# Flight_Controller2.net
KiCad netlist of a schematic drawn in Altium Designer
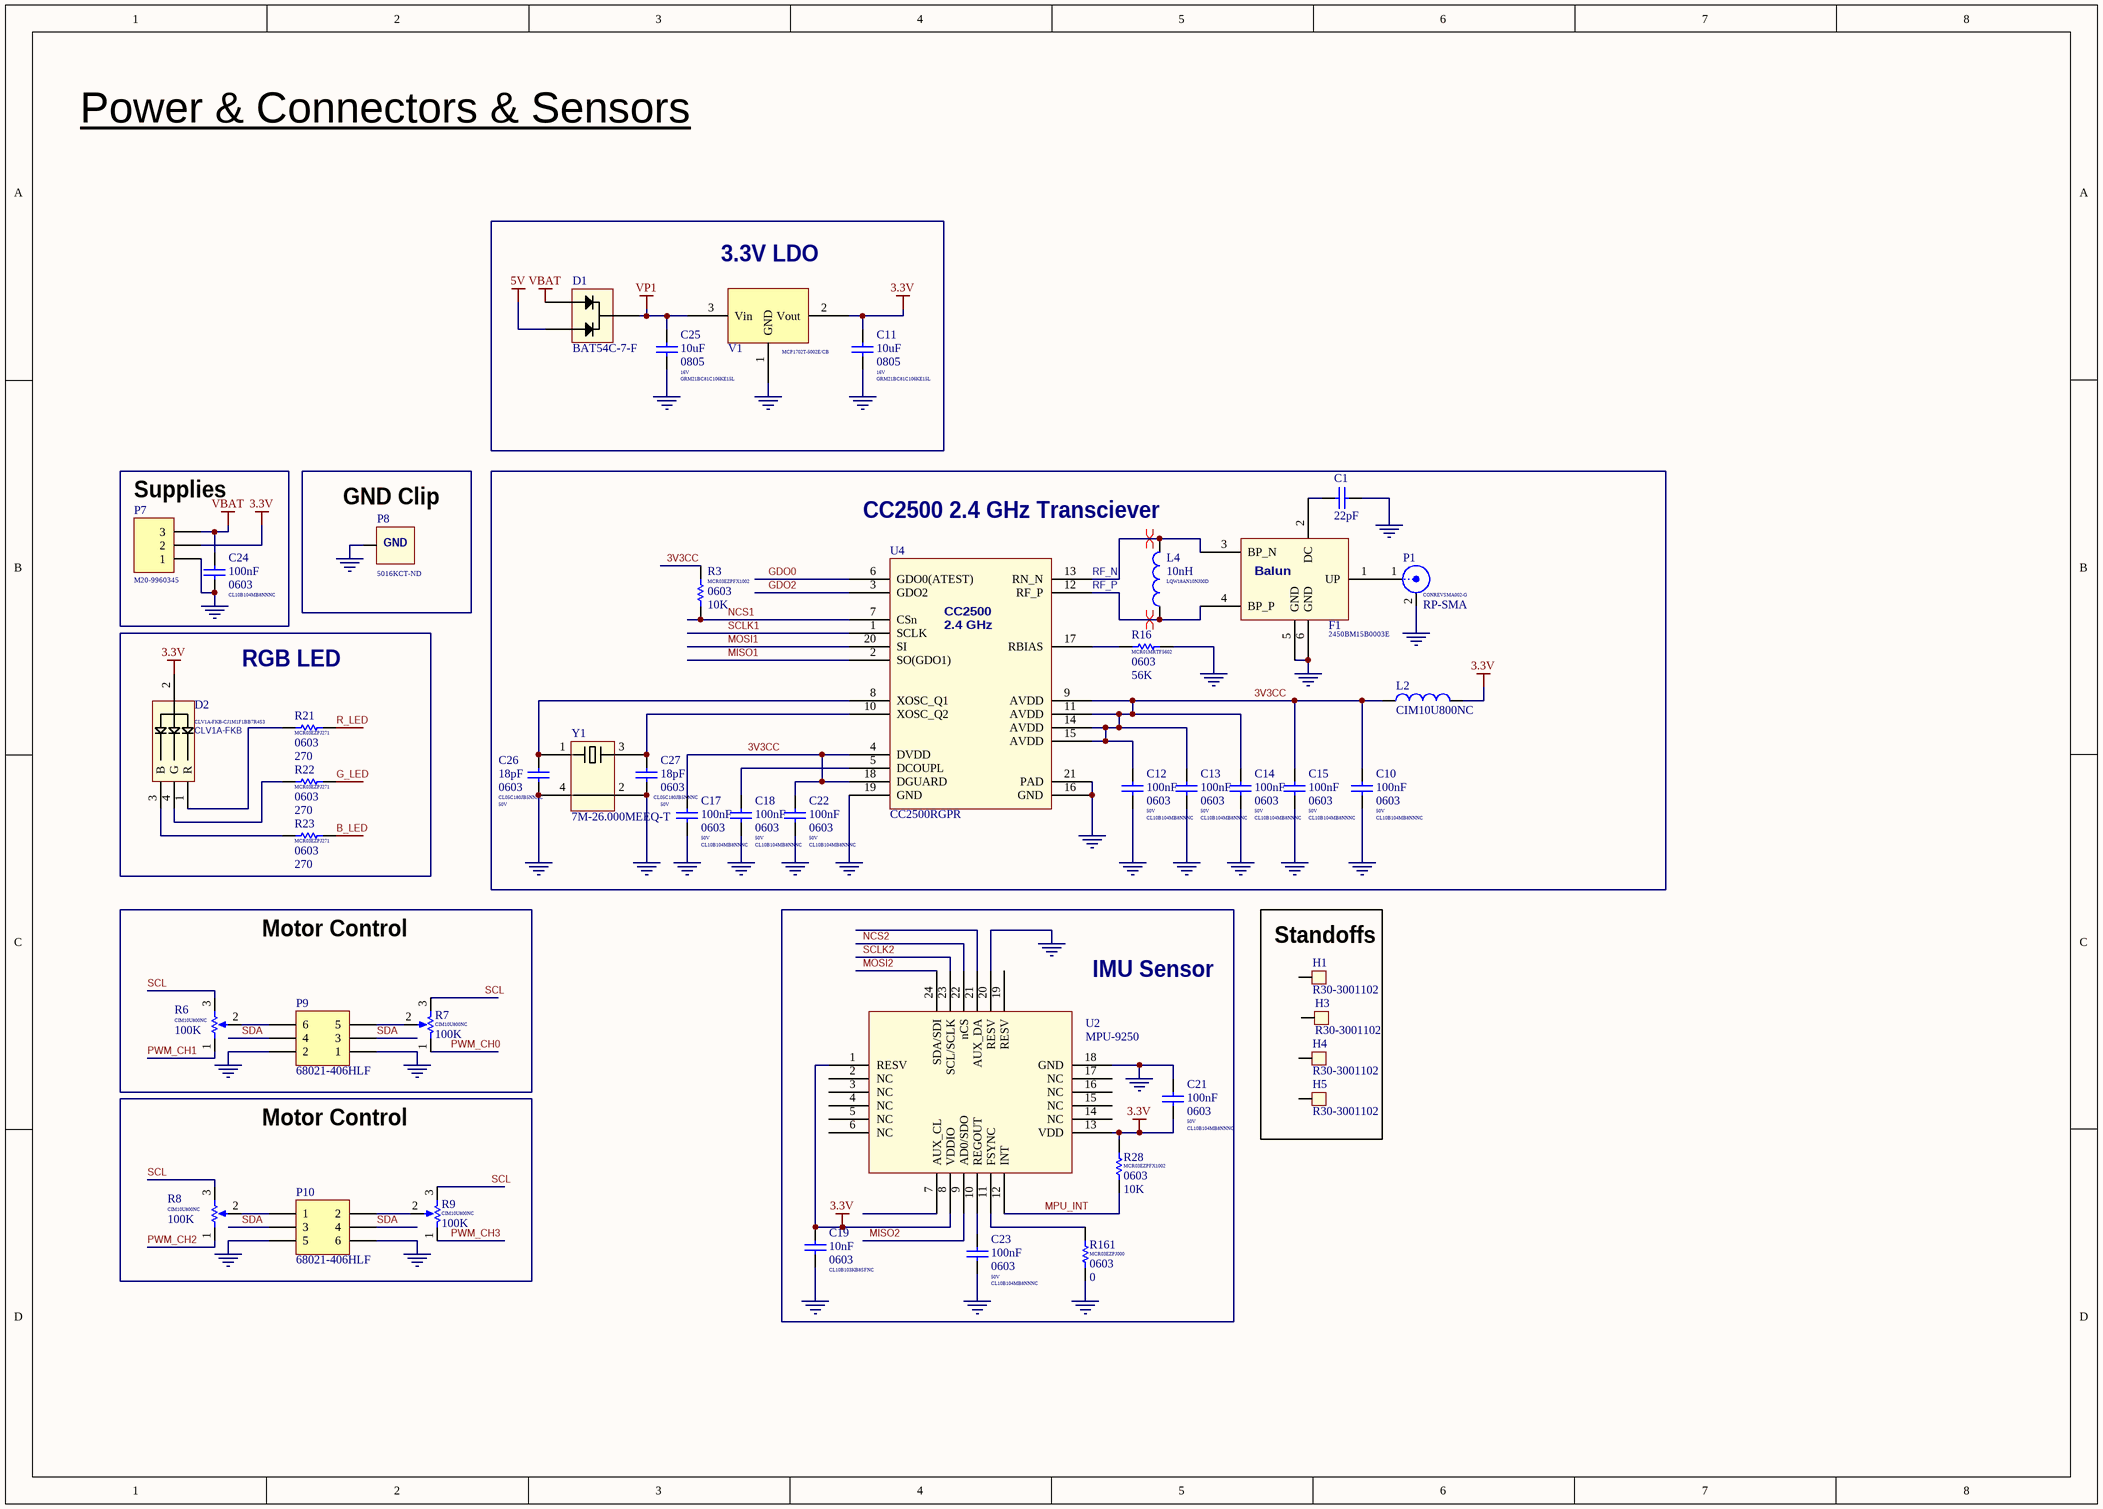
[diagram p0: Flight_Controller2.SchDoc]

(export (version "E")
  (design (tool "Eeschema 10.0.6"))
  (components
    (comp (ref "C1")
      (value "22pF")
      (footprint "1608[0603]C")
      (description "Capacitor (Semiconductor SIM Model)")
      (fields (field (name "Comment") "GRM1885C1H220FA01D") (field (name "PUBLISHER") "Altium Limited"))
      (libsource (lib "Miscellaneous Devices") (part "Cap Semi"))
    )
    (comp (ref "C10")
      (value "CL10B104MB8NNNC")
      (footprint "1608[0603]C")
      (description "Capacitor (Semiconductor SIM Model)")
      (fields
        (field (name "PACKAGEREFERENCE") "0603")
        (field (name "ALTIUM_VALUE") "100nF")
        (field (name "VOLTAGE") "50V")
      )
      (libsource (lib "Miscellaneous Devices") (part "Cap Semi"))
    )
    (comp (ref "C11")
      (value "GRM21BC81C106KE15L")
      (footprint "6-0805_MC")
      (description "Capacitor (Semiconductor SIM Model)")
      (fields
        (field (name "PACKAGEREFERENCE") "0805")
        (field (name "ALTIUM_VALUE") "10uF")
        (field (name "PART_NUMBER") "CL10B104MB8NNNC")
        (field (name "VOLTAGE") "16V")
      )
      (libsource (lib "Miscellaneous Devices") (part "Cap Semi"))
    )
    (comp (ref "C12")
      (value "CL10B104MB8NNNC")
      (footprint "1608[0603]C")
      (description "Capacitor (Semiconductor SIM Model)")
      (fields
        (field (name "PACKAGEREFERENCE") "0603")
        (field (name "ALTIUM_VALUE") "100nF")
        (field (name "VOLTAGE") "50V")
      )
      (libsource (lib "Miscellaneous Devices") (part "Cap Semi"))
    )
    (comp (ref "C13")
      (value "CL10B104MB8NNNC")
      (footprint "1608[0603]C")
      (description "Capacitor (Semiconductor SIM Model)")
      (fields
        (field (name "PACKAGEREFERENCE") "0603")
        (field (name "ALTIUM_VALUE") "100nF")
        (field (name "VOLTAGE") "50V")
      )
      (libsource (lib "Miscellaneous Devices") (part "Cap Semi"))
    )
    (comp (ref "C14")
      (value "CL10B104MB8NNNC")
      (footprint "1608[0603]C")
      (description "Capacitor (Semiconductor SIM Model)")
      (fields
        (field (name "PACKAGEREFERENCE") "0603")
        (field (name "ALTIUM_VALUE") "100nF")
        (field (name "VOLTAGE") "50V")
      )
      (libsource (lib "Miscellaneous Devices") (part "Cap Semi"))
    )
    (comp (ref "C15")
      (value "CL10B104MB8NNNC")
      (footprint "1608[0603]C")
      (description "Capacitor (Semiconductor SIM Model)")
      (fields
        (field (name "PACKAGEREFERENCE") "0603")
        (field (name "ALTIUM_VALUE") "100nF")
        (field (name "VOLTAGE") "50V")
      )
      (libsource (lib "Miscellaneous Devices") (part "Cap Semi"))
    )
    (comp (ref "C17")
      (value "CL10B104MB8NNNC")
      (footprint "1608[0603]C")
      (description "Capacitor (Semiconductor SIM Model)")
      (fields
        (field (name "PACKAGEREFERENCE") "0603")
        (field (name "ALTIUM_VALUE") "100nF")
        (field (name "VOLTAGE") "50V")
      )
      (libsource (lib "Miscellaneous Devices") (part "Cap Semi"))
    )
    (comp (ref "C18")
      (value "CL10B104MB8NNNC")
      (footprint "1608[0603]C")
      (description "Capacitor (Semiconductor SIM Model)")
      (fields
        (field (name "PACKAGEREFERENCE") "0603")
        (field (name "ALTIUM_VALUE") "100nF")
        (field (name "VOLTAGE") "50V")
      )
      (libsource (lib "Miscellaneous Devices") (part "Cap Semi"))
    )
    (comp (ref "C19")
      (value "CL10B103KB8SFNC")
      (footprint "1608[0603]C")
      (description "Capacitor (Semiconductor SIM Model)")
      (fields
        (field (name "PACKAGEREFERENCE") "0603")
        (field (name "ALTIUM_VALUE") "10nF")
        (field (name "PUBLISHER") "Altium Limited")
      )
      (libsource (lib "Miscellaneous Devices") (part "Cap Semi"))
    )
    (comp (ref "C21")
      (value "CL10B104MB8NNNC")
      (footprint "1608[0603]C")
      (description "Capacitor (Semiconductor SIM Model)")
      (fields
        (field (name "PACKAGEREFERENCE") "0603")
        (field (name "ALTIUM_VALUE") "100nF")
        (field (name "VOLTAGE") "50V")
      )
      (libsource (lib "Miscellaneous Devices") (part "Cap Semi"))
    )
    (comp (ref "C22")
      (value "CL10B104MB8NNNC")
      (footprint "1608[0603]C")
      (description "Capacitor (Semiconductor SIM Model)")
      (fields
        (field (name "PACKAGEREFERENCE") "0603")
        (field (name "ALTIUM_VALUE") "100nF")
        (field (name "VOLTAGE") "50V")
      )
      (libsource (lib "Miscellaneous Devices") (part "Cap Semi"))
    )
    (comp (ref "C23")
      (value "CL10B104MB8NNNC")
      (footprint "1608[0603]C")
      (description "Capacitor (Semiconductor SIM Model)")
      (fields
        (field (name "PACKAGEREFERENCE") "0603")
        (field (name "ALTIUM_VALUE") "100nF")
        (field (name "VOLTAGE") "50V")
      )
      (libsource (lib "Miscellaneous Devices") (part "Cap Semi"))
    )
    (comp (ref "C24")
      (value "CL10B104MB8NNNC")
      (footprint "1608[0603]C")
      (description "Capacitor (Semiconductor SIM Model)")
      (fields (field (name "PACKAGEREFERENCE") "0603") (field (name "ALTIUM_VALUE") "100nF"))
      (libsource (lib "Miscellaneous Devices") (part "Cap Semi"))
    )
    (comp (ref "C25")
      (value "GRM21BC81C106KE15L")
      (footprint "6-0805_MC")
      (description "Capacitor (Semiconductor SIM Model)")
      (fields
        (field (name "PACKAGEREFERENCE") "0805")
        (field (name "ALTIUM_VALUE") "10uF")
        (field (name "PART_NUMBER") "CL10B104MB8NNNC")
        (field (name "VOLTAGE") "16V")
      )
      (libsource (lib "Miscellaneous Devices") (part "Cap Semi"))
    )
    (comp (ref "C26")
      (value "CL05C180JB5NNNC")
      (footprint "1608[0603]C")
      (description "Capacitor (Semiconductor SIM Model)")
      (fields
        (field (name "PACKAGEREFERENCE") "0603")
        (field (name "ALTIUM_VALUE") "18pF")
        (field (name "VOLTAGE") "50V")
      )
      (libsource (lib "Miscellaneous Devices") (part "Cap Semi"))
    )
    (comp (ref "C27")
      (value "CL05C180JB5NNNC")
      (footprint "1608[0603]C")
      (description "Capacitor (Semiconductor SIM Model)")
      (fields
        (field (name "PACKAGEREFERENCE") "0603")
        (field (name "ALTIUM_VALUE") "18pF")
        (field (name "VOLTAGE") "50V")
      )
      (libsource (lib "Miscellaneous Devices") (part "Cap Semi"))
    )
    (comp (ref "D1")
      (value "BAT54C-7-F")
      (footprint "SOT-23B_M_3D")
      (description "Bat45C")
      (libsource (lib "bat45") (part "Bat45C"))
    )
    (comp (ref "D2")
      (value "CLV1A-FKB-CJ1M1F1BB7R4S3")
      (footprint "CLV1A-FKB_RGB_3D")
      (description "SMT RGB LED")
      (fields (field (name "ALTIUM_UNNAMED_1") "CLV1A-FKB"))
      (libsource (lib "RGB_LED") (part "RGB_LED_SMT"))
    )
    (comp (ref "F1")
      (value "2450BM15B0003E")
      (footprint "Balun")
      (description "2450BM15B0003")
      (libsource (lib "2450BM15B0003") (part "BALUN_2_4_GHZ"))
    )
    (comp (ref "H1")
      (value "R30-3001102")
      (footprint "M3_Standoff_3")
      (description "stand_off")
      (libsource (lib "pcb_standoff") (part "stand_off"))
    )
    (comp (ref "H3")
      (value "R30-3001102")
      (footprint "M3_Standoff_3")
      (description "stand_off")
      (libsource (lib "pcb_standoff") (part "stand_off"))
    )
    (comp (ref "H4")
      (value "R30-3001102")
      (footprint "M3_Standoff_3")
      (description "stand_off")
      (libsource (lib "pcb_standoff") (part "stand_off"))
    )
    (comp (ref "H5")
      (value "R30-3001102")
      (footprint "M3_Standoff_3")
      (description "stand_off")
      (libsource (lib "pcb_standoff") (part "stand_off"))
    )
    (comp (ref "L2")
      (value "CIM10U800NC")
      (footprint "1608[0603]L")
      (description "Inductor")
      (libsource (lib "Miscellaneous Devices") (part "Inductor"))
    )
    (comp (ref "L4")
      (value "LQW18AN10NJ00D")
      (footprint "1608[0603]L")
      (description "Inductor")
      (fields (field (name "ALTIUM_VALUE") "10nH"))
      (libsource (lib "Miscellaneous Devices") (part "Inductor"))
    )
    (comp (ref "P1")
      (value "CONREVSMA002-G")
      (footprint "SMA1")
      (description "SMB Straight Connector")
      (fields (field (name "PART #") "5-1814832-1") (field (name "SMA") "RP-SMA"))
      (libsource (lib "Miscellaneous Connectors") (part "SMB"))
    )
    (comp (ref "P7")
      (value "M20-9960345")
      (footprint "HDR1X3")
      (description "Header, 3-Pin")
      (fields (field (name "PUBLISHER") "Altium Limited"))
      (libsource (lib "Miscellaneous Connectors") (part "Header 3"))
    )
    (comp (ref "P8")
      (value "5016KCT-ND")
      (footprint "GND_CLIP3")
      (description "GND_CLIP")
      (libsource (lib "GND_CLIP") (part "GND_CLIP"))
    )
    (comp (ref "P9")
      (value "68021-406HLF")
      (footprint "HDR2X3_3D2")
      (description "Header, 3-Pin, Dual row")
      (fields (field (name "PUBLISHER") "Altium Limited"))
      (libsource (lib "Miscellaneous Connectors") (part "Header 3X2"))
    )
    (comp (ref "P10")
      (value "68021-406HLF")
      (footprint "HDR2X3_3D2")
      (description "Header, 3-Pin, Dual row")
      (fields (field (name "PUBLISHER") "Altium Limited"))
      (libsource (lib "") (part "Header 3X2_1"))
    )
    (comp (ref "R3")
      (value "MCR03EZPFX1002")
      (footprint "1608[0603]R")
      (description "Resistor")
      (fields
        (field (name "PACKAGEREFERENCE") "0603")
        (field (name "ALTIUM_VALUE") "10K")
        (field (name "PART_NUMBER") "MCR03ERTJ102")
      )
      (libsource (lib "Miscellaneous Devices") (part "Res1"))
    )
    (comp (ref "R6")
      (value "CIM10U800NC")
      (footprint "1608[0603]TRI")
      (description "Potentiometer")
      (fields (field (name "ALTIUM_VALUE") "100K") (field (name "PUBLISHER") "Altium Limited"))
      (libsource (lib "Miscellaneous Devices") (part "RPot"))
    )
    (comp (ref "R7")
      (value "CIM10U800NC")
      (footprint "1608[0603]TRI")
      (description "Potentiometer")
      (fields (field (name "ALTIUM_VALUE") "100K") (field (name "PUBLISHER") "Altium Limited"))
      (libsource (lib "Miscellaneous Devices") (part "RPot"))
    )
    (comp (ref "R8")
      (value "CIM10U800NC")
      (footprint "1608[0603]TRI")
      (description "Potentiometer")
      (fields (field (name "ALTIUM_VALUE") "100K") (field (name "PUBLISHER") "Altium Limited"))
      (libsource (lib "Miscellaneous Devices") (part "RPot"))
    )
    (comp (ref "R9")
      (value "CIM10U800NC")
      (footprint "1608[0603]TRI")
      (description "Potentiometer")
      (fields (field (name "ALTIUM_VALUE") "100K") (field (name "PUBLISHER") "Altium Limited"))
      (libsource (lib "Miscellaneous Devices") (part "RPot"))
    )
    (comp (ref "R16")
      (value "MCR01MRTF5602")
      (footprint "1608[0603]R")
      (description "Resistor")
      (fields
        (field (name "PACKAGEREFERENCE") "0603")
        (field (name "ALTIUM_VALUE") "56K")
        (field (name "PART_NUMBER") "MCR03ERTJ102")
      )
      (libsource (lib "Miscellaneous Devices") (part "Res1"))
    )
    (comp (ref "R21")
      (value "MCR03EZPJ271")
      (footprint "1608[0603]R")
      (description "Resistor")
      (fields
        (field (name "PACKAGEREFERENCE") "0603")
        (field (name "ALTIUM_VALUE") "270")
        (field (name "PART_NUMBER") "MCR03ERTJ102")
      )
      (libsource (lib "Miscellaneous Devices") (part "Res1"))
    )
    (comp (ref "R22")
      (value "MCR03EZPJ271")
      (footprint "1608[0603]R")
      (description "Resistor")
      (fields
        (field (name "PACKAGEREFERENCE") "0603")
        (field (name "ALTIUM_VALUE") "270")
        (field (name "PART_NUMBER") "MCR03ERTJ102")
      )
      (libsource (lib "Miscellaneous Devices") (part "Res1"))
    )
    (comp (ref "R23")
      (value "MCR03EZPJ271")
      (footprint "1608[0603]R")
      (description "Resistor")
      (fields
        (field (name "PACKAGEREFERENCE") "0603")
        (field (name "ALTIUM_VALUE") "270")
        (field (name "PART_NUMBER") "MCR03ERTJ102")
      )
      (libsource (lib "Miscellaneous Devices") (part "Res1"))
    )
    (comp (ref "R28")
      (value "MCR03EZPFX1002")
      (footprint "1608[0603]R")
      (description "Resistor")
      (fields
        (field (name "PACKAGEREFERENCE") "0603")
        (field (name "ALTIUM_VALUE") "10K")
        (field (name "PART_NUMBER") "MCR03ERTJ102")
      )
      (libsource (lib "Miscellaneous Devices") (part "Res1"))
    )
    (comp (ref "R161")
      (value "MCR03EZPJ000")
      (footprint "1608[0603]R")
      (description "Resistor")
      (fields
        (field (name "PACKAGEREFERENCE") "0603")
        (field (name "ALTIUM_VALUE") "0")
        (field (name "PART_NUMBER") "MCR03ERTJ102")
      )
      (libsource (lib "Miscellaneous Devices") (part "Res1"))
    )
    (comp (ref "U2")
      (value "MPU-9250")
      (footprint "QFN-24/3MM")
      (libsource (lib "MPU9250") (part "MPU-9250_LIB"))
    )
    (comp (ref "U4")
      (value "CC2500RGPR")
      (footprint "QFN50P400X400-20VM")
      (description "CC2500_2_4_ghz")
      (libsource (lib "CC2500") (part "CC2500_2_4_ghz"))
    )
    (comp (ref "V1")
      (value "MCP1702T-5002E/CB")
      (footprint "SOT-23B_M_3D")
      (description "MCP1700 3.3V REG")
      (libsource (lib "MCP1700") (part "MCP1700"))
    )
    (comp (ref "Y1")
      (value "7M-26.000MEEQ-T")
      (footprint "3225_Crystal")
      (description "26 MHz Crystal 3225")
      (libsource (lib "12MHz_micro_crystal") (part "12MHz_Crystal"))
    )
  )
  (nets
    (net (code "1") (name "/3V3CC") (class "Default")
      (node (ref "C10") (pin "2") (pinfunction "2_2") (pintype "passive"))
      (node (ref "C12") (pin "2") (pinfunction "2_2") (pintype "passive"))
      (node (ref "C13") (pin "2") (pinfunction "2_2") (pintype "passive"))
      (node (ref "C14") (pin "2") (pinfunction "2_2") (pintype "passive"))
      (node (ref "C15") (pin "2") (pinfunction "2_2") (pintype "passive"))
      (node (ref "C17") (pin "2") (pinfunction "2_2") (pintype "passive"))
      (node (ref "C22") (pin "2") (pinfunction "2_2") (pintype "passive"))
      (node (ref "L2") (pin "2") (pinfunction "2_2") (pintype "passive"))
      (node (ref "R3") (pin "2") (pinfunction "2_2") (pintype "passive"))
      (node (ref "U4") (pin "11") (pinfunction "AVDD_11") (pintype "passive"))
      (node (ref "U4") (pin "14") (pinfunction "AVDD_14") (pintype "passive"))
      (node (ref "U4") (pin "15") (pinfunction "AVDD_15") (pintype "passive"))
      (node (ref "U4") (pin "18") (pinfunction "DGUARD_18") (pintype "passive"))
      (node (ref "U4") (pin "4") (pinfunction "DVDD_4") (pintype "passive"))
      (node (ref "U4") (pin "9") (pinfunction "AVDD_9") (pintype "passive"))
    )
    (net (code "2") (name "/B_LED") (class "Default")
      (node (ref "R23") (pin "2") (pinfunction "2_2") (pintype "passive"))
    )
    (net (code "3") (name "/GDO0") (class "Default")
      (node (ref "U4") (pin "6") (pinfunction "GDO0(ATEST)_6") (pintype "passive"))
    )
    (net (code "4") (name "/GDO2") (class "Default")
      (node (ref "U4") (pin "3") (pinfunction "GDO2_3") (pintype "passive"))
    )
    (net (code "5") (name "/G_LED") (class "Default")
      (node (ref "R22") (pin "2") (pinfunction "2_2") (pintype "passive"))
    )
    (net (code "6") (name "/MISO1") (class "Default")
      (node (ref "U4") (pin "2") (pinfunction "SO(GDO1)_2") (pintype "passive"))
    )
    (net (code "7") (name "/MISO2") (class "Default")
      (node (ref "U2") (pin "9") (pinfunction "AD0/SDO_9") (pintype "passive"))
    )
    (net (code "8") (name "/MOSI1") (class "Default")
      (node (ref "U4") (pin "20") (pinfunction "SI_20") (pintype "passive"))
    )
    (net (code "9") (name "/MOSI2") (class "Default")
      (node (ref "U2") (pin "24") (pinfunction "SDA/SDI_24") (pintype "passive"))
    )
    (net (code "10") (name "/MPU_INT") (class "Default")
      (node (ref "R28") (pin "1") (pinfunction "1_1") (pintype "passive"))
      (node (ref "U2") (pin "12") (pinfunction "INT_12") (pintype "passive"))
    )
    (net (code "11") (name "/NCS1") (class "Default")
      (node (ref "R3") (pin "1") (pinfunction "1_1") (pintype "passive"))
      (node (ref "U4") (pin "7") (pinfunction "CSn_7") (pintype "passive"))
    )
    (net (code "12") (name "/NCS2") (class "Default")
      (node (ref "U2") (pin "22") (pinfunction "nCS_22") (pintype "passive"))
    )
    (net (code "13") (name "/PWM_CH0") (class "Default")
      (node (ref "R7") (pin "1") (pinfunction "1_1") (pintype "passive"))
    )
    (net (code "14") (name "/PWM_CH1") (class "Default")
      (node (ref "R6") (pin "1") (pinfunction "1_1") (pintype "passive"))
    )
    (net (code "15") (name "/PWM_CH2") (class "Default")
      (node (ref "R8") (pin "1") (pinfunction "1_1") (pintype "passive"))
    )
    (net (code "16") (name "/PWM_CH3") (class "Default")
      (node (ref "R9") (pin "1") (pinfunction "1_1") (pintype "passive"))
    )
    (net (code "17") (name "/RF_N") (class "Default")
      (node (ref "F1") (pin "3") (pinfunction "BP_N_3") (pintype "passive"))
      (node (ref "L4") (pin "1") (pinfunction "1_1") (pintype "passive"))
      (node (ref "U4") (pin "13") (pinfunction "RN_N_13") (pintype "passive"))
    )
    (net (code "18") (name "/RF_P") (class "Default")
      (node (ref "F1") (pin "4") (pinfunction "BP_P_4") (pintype "passive"))
      (node (ref "L4") (pin "2") (pinfunction "2_2") (pintype "passive"))
      (node (ref "U4") (pin "12") (pinfunction "RF_P_12") (pintype "passive"))
    )
    (net (code "19") (name "/R_LED") (class "Default")
      (node (ref "R21") (pin "2") (pinfunction "2_2") (pintype "passive"))
    )
    (net (code "20") (name "/SCL") (class "Default")
      (node (ref "R6") (pin "3") (pinfunction "2_3") (pintype "passive"))
      (node (ref "R7") (pin "3") (pinfunction "2_3") (pintype "passive"))
      (node (ref "R8") (pin "3") (pinfunction "2_3") (pintype "passive"))
      (node (ref "R9") (pin "3") (pinfunction "2_3") (pintype "passive"))
    )
    (net (code "21") (name "/SCLK1") (class "Default")
      (node (ref "U4") (pin "1") (pinfunction "SCLK_1") (pintype "passive"))
    )
    (net (code "22") (name "/SCLK2") (class "Default")
      (node (ref "U2") (pin "23") (pinfunction "SCL/SCLK_23") (pintype "passive"))
    )
    (net (code "23") (name "/SDA") (class "Default")
      (node (ref "P10") (pin "3") (pinfunction "3_3") (pintype "passive"))
      (node (ref "P10") (pin "4") (pinfunction "4_4") (pintype "passive"))
      (node (ref "P9") (pin "3") (pinfunction "3_3") (pintype "passive"))
      (node (ref "P9") (pin "4") (pinfunction "4_4") (pintype "passive"))
    )
    (net (code "24") (name "3.3V") (class "Default")
      (node (ref "C11") (pin "2") (pinfunction "2_2") (pintype "passive"))
      (node (ref "C19") (pin "2") (pinfunction "2_2") (pintype "passive"))
      (node (ref "C21") (pin "1") (pinfunction "1_1") (pintype "passive"))
      (node (ref "D2") (pin "2") (pinfunction "V+_2") (pintype "passive"))
      (node (ref "L2") (pin "1") (pinfunction "1_1") (pintype "passive"))
      (node (ref "P7") (pin "2") (pinfunction "2_2") (pintype "passive"))
      (node (ref "R28") (pin "2") (pinfunction "2_2") (pintype "passive"))
      (node (ref "U2") (pin "1") (pinfunction "RESV_1") (pintype "passive"))
      (node (ref "U2") (pin "13") (pinfunction "VDD_13") (pintype "passive"))
      (node (ref "U2") (pin "8") (pinfunction "VDDIO_8") (pintype "passive"))
      (node (ref "V1") (pin "2") (pinfunction "Vout_2") (pintype "passive"))
    )
    (net (code "25") (name "5V") (class "Default")
      (node (ref "D1") (pin "2") (pinfunction "0_2") (pintype "passive"))
    )
    (net (code "26") (name "GND") (class "Default")
      (node (ref "C1") (pin "2") (pinfunction "2_2") (pintype "passive"))
      (node (ref "C10") (pin "1") (pinfunction "1_1") (pintype "passive"))
      (node (ref "C11") (pin "1") (pinfunction "1_1") (pintype "passive"))
      (node (ref "C12") (pin "1") (pinfunction "1_1") (pintype "passive"))
      (node (ref "C13") (pin "1") (pinfunction "1_1") (pintype "passive"))
      (node (ref "C14") (pin "1") (pinfunction "1_1") (pintype "passive"))
      (node (ref "C15") (pin "1") (pinfunction "1_1") (pintype "passive"))
      (node (ref "C17") (pin "1") (pinfunction "1_1") (pintype "passive"))
      (node (ref "C18") (pin "1") (pinfunction "1_1") (pintype "passive"))
      (node (ref "C19") (pin "1") (pinfunction "1_1") (pintype "passive"))
      (node (ref "C21") (pin "2") (pinfunction "2_2") (pintype "passive"))
      (node (ref "C22") (pin "1") (pinfunction "1_1") (pintype "passive"))
      (node (ref "C23") (pin "1") (pinfunction "1_1") (pintype "passive"))
      (node (ref "C24") (pin "1") (pinfunction "1_1") (pintype "passive"))
      (node (ref "C25") (pin "1") (pinfunction "1_1") (pintype "passive"))
      (node (ref "C26") (pin "1") (pinfunction "1_1") (pintype "passive"))
      (node (ref "C27") (pin "1") (pinfunction "1_1") (pintype "passive"))
      (node (ref "F1") (pin "5") (pinfunction "GND_5") (pintype "passive"))
      (node (ref "F1") (pin "6") (pinfunction "GND_6") (pintype "passive"))
      (node (ref "P1") (pin "2") (pinfunction "Y_2") (pintype "passive"))
      (node (ref "P10") (pin "5") (pinfunction "5_5") (pintype "passive"))
      (node (ref "P10") (pin "6") (pinfunction "6_6") (pintype "passive"))
      (node (ref "P7") (pin "1") (pinfunction "1_1") (pintype "passive"))
      (node (ref "P8") (pin "1") (pinfunction "GND_1") (pintype "passive"))
      (node (ref "P9") (pin "1") (pinfunction "1_1") (pintype "passive"))
      (node (ref "P9") (pin "2") (pinfunction "2_2") (pintype "passive"))
      (node (ref "R16") (pin "1") (pinfunction "1_1") (pintype "passive"))
      (node (ref "R161") (pin "2") (pinfunction "2_2") (pintype "passive"))
      (node (ref "U2") (pin "18") (pinfunction "GND_18") (pintype "passive"))
      (node (ref "U2") (pin "20") (pinfunction "RESV_20") (pintype "passive"))
      (node (ref "U4") (pin "16") (pinfunction "GND_16") (pintype "passive"))
      (node (ref "U4") (pin "19") (pinfunction "GND_19") (pintype "passive"))
      (node (ref "U4") (pin "21") (pinfunction "PAD_21") (pintype "passive"))
      (node (ref "V1") (pin "1") (pinfunction "GND_1") (pintype "passive"))
      (node (ref "Y1") (pin "2") (pinfunction "GND_2") (pintype "passive"))
      (node (ref "Y1") (pin "4") (pinfunction "GND_4") (pintype "passive"))
    )
    (net (code "27") (name "Net-(D2-B)") (class "Default")
      (node (ref "D2") (pin "3") (pinfunction "B_3") (pintype "passive"))
      (node (ref "R23") (pin "1") (pinfunction "1_1") (pintype "passive"))
    )
    (net (code "28") (name "Net-(D2-G)") (class "Default")
      (node (ref "D2") (pin "4") (pinfunction "G_4") (pintype "passive"))
      (node (ref "R22") (pin "1") (pinfunction "1_1") (pintype "passive"))
    )
    (net (code "29") (name "Net-(D2-R)") (class "Default")
      (node (ref "D2") (pin "1") (pinfunction "R_1") (pintype "passive"))
      (node (ref "R21") (pin "1") (pinfunction "1_1") (pintype "passive"))
    )
    (net (code "30") (name "Net-(F1-DC)") (class "Default")
      (node (ref "C1") (pin "1") (pinfunction "1_1") (pintype "passive"))
      (node (ref "F1") (pin "2") (pinfunction "DC_2") (pintype "passive"))
    )
    (net (code "31") (name "Net-(F1-UP)") (class "Default")
      (node (ref "F1") (pin "1") (pinfunction "UP_1") (pintype "passive"))
      (node (ref "P1") (pin "1") (pinfunction "X_1") (pintype "passive"))
    )
    (net (code "32") (name "Net-(R6-3)") (class "Default")
      (node (ref "P9") (pin "6") (pinfunction "6_6") (pintype "passive"))
      (node (ref "R6") (pin "2") (pinfunction "3_2") (pintype "passive"))
    )
    (net (code "33") (name "Net-(R7-3)") (class "Default")
      (node (ref "P9") (pin "5") (pinfunction "5_5") (pintype "passive"))
      (node (ref "R7") (pin "2") (pinfunction "3_2") (pintype "passive"))
    )
    (net (code "34") (name "Net-(R8-3)") (class "Default")
      (node (ref "P10") (pin "1") (pinfunction "1_1") (pintype "passive"))
      (node (ref "R8") (pin "2") (pinfunction "3_2") (pintype "passive"))
    )
    (net (code "35") (name "Net-(R9-3)") (class "Default")
      (node (ref "P10") (pin "2") (pinfunction "2_2") (pintype "passive"))
      (node (ref "R9") (pin "2") (pinfunction "3_2") (pintype "passive"))
    )
    (net (code "36") (name "Net-(U2-FSYNC)") (class "Default")
      (node (ref "R161") (pin "1") (pinfunction "1_1") (pintype "passive"))
      (node (ref "U2") (pin "11") (pinfunction "FSYNC_11") (pintype "passive"))
    )
    (net (code "37") (name "Net-(U2-REGOUT)") (class "Default")
      (node (ref "C23") (pin "2") (pinfunction "2_2") (pintype "passive"))
      (node (ref "U2") (pin "10") (pinfunction "REGOUT_10") (pintype "passive"))
    )
    (net (code "38") (name "Net-(U4-DCOUPL)") (class "Default")
      (node (ref "C18") (pin "2") (pinfunction "2_2") (pintype "passive"))
      (node (ref "U4") (pin "5") (pinfunction "DCOUPL_5") (pintype "passive"))
    )
    (net (code "39") (name "Net-(U4-RBIAS)") (class "Default")
      (node (ref "R16") (pin "2") (pinfunction "2_2") (pintype "passive"))
      (node (ref "U4") (pin "17") (pinfunction "RBIAS_17") (pintype "passive"))
    )
    (net (code "40") (name "Net-(U4-XOSC_Q1)") (class "Default")
      (node (ref "C26") (pin "2") (pinfunction "2_2") (pintype "passive"))
      (node (ref "U4") (pin "8") (pinfunction "XOSC_Q1_8") (pintype "passive"))
      (node (ref "Y1") (pin "1") (pinfunction "X1_1") (pintype "passive"))
    )
    (net (code "41") (name "Net-(U4-XOSC_Q2)") (class "Default")
      (node (ref "C27") (pin "2") (pinfunction "2_2") (pintype "passive"))
      (node (ref "U4") (pin "10") (pinfunction "XOSC_Q2_10") (pintype "passive"))
      (node (ref "Y1") (pin "3") (pinfunction "X2_3") (pintype "passive"))
    )
    (net (code "42") (name "VBAT") (class "Default")
      (node (ref "C24") (pin "2") (pinfunction "2_2") (pintype "passive"))
      (node (ref "D1") (pin "1") (pinfunction "0_1") (pintype "passive"))
      (node (ref "P7") (pin "3") (pinfunction "3_3") (pintype "passive"))
    )
    (net (code "43") (name "VP1") (class "Default")
      (node (ref "C25") (pin "2") (pinfunction "2_2") (pintype "passive"))
      (node (ref "D1") (pin "3") (pinfunction "0_3") (pintype "passive"))
      (node (ref "V1") (pin "3") (pinfunction "Vin_3") (pintype "passive"))
    )
    (net (code "44") (name "unconnected-(H1-0-Pad1)") (class "Default")
      (node (ref "H1") (pin "1") (pinfunction "0_1") (pintype "passive"))
    )
    (net (code "45") (name "unconnected-(H3-0-Pad1)") (class "Default")
      (node (ref "H3") (pin "1") (pinfunction "0_1") (pintype "passive"))
    )
    (net (code "46") (name "unconnected-(H4-0-Pad1)") (class "Default")
      (node (ref "H4") (pin "1") (pinfunction "0_1") (pintype "passive"))
    )
    (net (code "47") (name "unconnected-(H5-0-Pad1)") (class "Default")
      (node (ref "H5") (pin "1") (pinfunction "0_1") (pintype "passive"))
    )
    (net (code "48") (name "unconnected-(U2-AUX_CL-Pad7)") (class "Default")
      (node (ref "U2") (pin "7") (pinfunction "AUX_CL_7") (pintype "passive"))
    )
    (net (code "49") (name "unconnected-(U2-AUX_DA-Pad21)") (class "Default")
      (node (ref "U2") (pin "21") (pinfunction "AUX_DA_21") (pintype "passive"))
    )
    (net (code "50") (name "unconnected-(U2-NC-Pad2)") (class "Default")
      (node (ref "U2") (pin "2") (pinfunction "NC_2") (pintype "passive"))
    )
    (net (code "51") (name "unconnected-(U2-NC-Pad3)") (class "Default")
      (node (ref "U2") (pin "3") (pinfunction "NC_3") (pintype "passive"))
    )
    (net (code "52") (name "unconnected-(U2-NC-Pad4)") (class "Default")
      (node (ref "U2") (pin "4") (pinfunction "NC_4") (pintype "passive"))
    )
    (net (code "53") (name "unconnected-(U2-NC-Pad5)") (class "Default")
      (node (ref "U2") (pin "5") (pinfunction "NC_5") (pintype "passive"))
    )
    (net (code "54") (name "unconnected-(U2-NC-Pad6)") (class "Default")
      (node (ref "U2") (pin "6") (pinfunction "NC_6") (pintype "passive"))
    )
    (net (code "55") (name "unconnected-(U2-NC-Pad14)") (class "Default")
      (node (ref "U2") (pin "14") (pinfunction "NC_14") (pintype "passive"))
    )
    (net (code "56") (name "unconnected-(U2-NC-Pad15)") (class "Default")
      (node (ref "U2") (pin "15") (pinfunction "NC_15") (pintype "passive"))
    )
    (net (code "57") (name "unconnected-(U2-NC-Pad16)") (class "Default")
      (node (ref "U2") (pin "16") (pinfunction "NC_16") (pintype "passive"))
    )
    (net (code "58") (name "unconnected-(U2-NC-Pad17)") (class "Default")
      (node (ref "U2") (pin "17") (pinfunction "NC_17") (pintype "passive"))
    )
    (net (code "59") (name "unconnected-(U2-RESV-Pad19)") (class "Default")
      (node (ref "U2") (pin "19") (pinfunction "RESV_19") (pintype "passive"))
    )
  )
)
